# mcu_v05.net
KiCad netlist of a schematic drawn in EAGLE
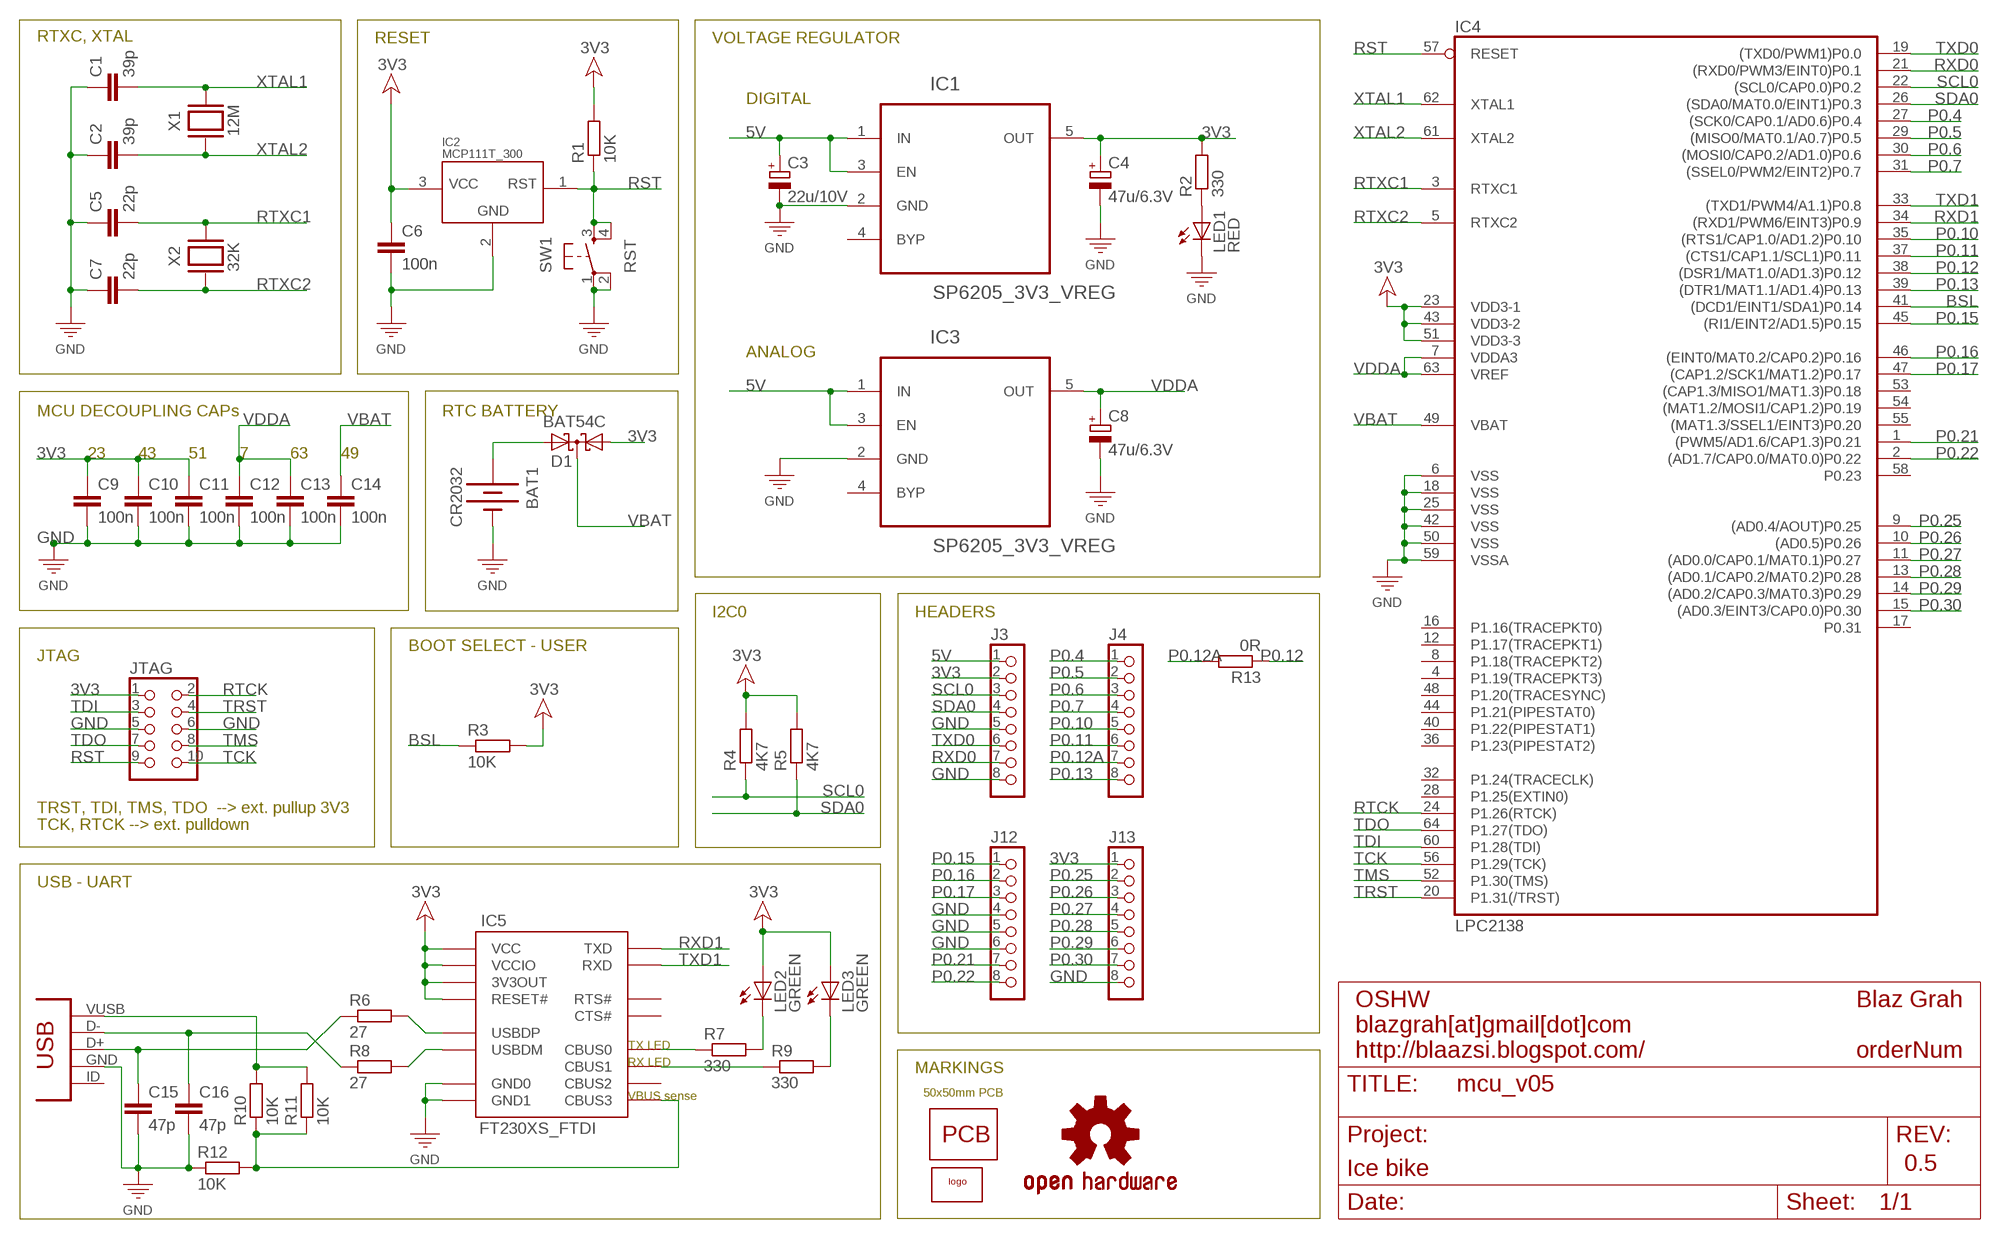
[diagram p0: schematic, sheet 1]

(export (version "E")
  (design (tool "Eeschema 10.0.6"))
  (components
    (comp (ref "BAT1")
      (value "CR2032")
      (footprint "eagle-import:BATTERY_20MM_SMD")
      (libsource (lib "eagle-import") (part "BATTERY20MM"))
    )
    (comp (ref "C1")
      (value "39p")
      (footprint "eagle-import:C0603")
      (libsource (lib "eagle-import") (part "C-EUC0603"))
    )
    (comp (ref "C2")
      (value "39p")
      (footprint "eagle-import:C0603")
      (libsource (lib "eagle-import") (part "C-EUC0603"))
    )
    (comp (ref "C3")
      (value "22u/10V")
      (footprint "eagle-import:SMC_B")
      (libsource (lib "eagle-import") (part "CAPACITOR_POL-SMC_B"))
    )
    (comp (ref "C4")
      (value "47u/6.3V")
      (footprint "eagle-import:SMC_B")
      (libsource (lib "eagle-import") (part "CAPACITOR_POL-SMC_B"))
    )
    (comp (ref "C5")
      (value "22p")
      (footprint "eagle-import:C0603")
      (libsource (lib "eagle-import") (part "C-EUC0603"))
    )
    (comp (ref "C6")
      (value "100n")
      (footprint "eagle-import:C0603")
      (libsource (lib "eagle-import") (part "C-EUC0603"))
    )
    (comp (ref "C7")
      (value "22p")
      (footprint "eagle-import:C0603")
      (libsource (lib "eagle-import") (part "C-EUC0603"))
    )
    (comp (ref "C8")
      (value "47u/6.3V")
      (footprint "eagle-import:SMC_B")
      (libsource (lib "eagle-import") (part "CAPACITOR_POL-SMC_B"))
    )
    (comp (ref "C9")
      (value "100n")
      (footprint "eagle-import:C0603")
      (libsource (lib "eagle-import") (part "C-EUC0603"))
    )
    (comp (ref "C10")
      (value "100n")
      (footprint "eagle-import:C0603")
      (libsource (lib "eagle-import") (part "C-EUC0603"))
    )
    (comp (ref "C11")
      (value "100n")
      (footprint "eagle-import:C0603")
      (libsource (lib "eagle-import") (part "C-EUC0603"))
    )
    (comp (ref "C12")
      (value "100n")
      (footprint "eagle-import:C0603")
      (libsource (lib "eagle-import") (part "C-EUC0603"))
    )
    (comp (ref "C13")
      (value "100n")
      (footprint "eagle-import:C0603")
      (libsource (lib "eagle-import") (part "C-EUC0603"))
    )
    (comp (ref "C14")
      (value "100n")
      (footprint "eagle-import:C0603")
      (libsource (lib "eagle-import") (part "C-EUC0603"))
    )
    (comp (ref "C15")
      (value "47p")
      (footprint "eagle-import:C0603")
      (libsource (lib "eagle-import") (part "C-EUC0603"))
    )
    (comp (ref "C16")
      (value "47p")
      (footprint "eagle-import:C0603")
      (libsource (lib "eagle-import") (part "C-EUC0603"))
    )
    (comp (ref "D1")
      (value "BAT54C")
      (footprint "eagle-import:SOT23")
      (libsource (lib "eagle-import") (part "BAT54C"))
    )
    (comp (ref "DOC")
      (value "FRAME_DINA4_L")
      (footprint "eagle-import:DP_LOGO")
      (fields
        (field (name "AUTHOR") "Blaz Grah")
        (field (name "DATE") "23.4.2012")
        (field (name "LICENSE") "OSHW")
        (field (name "PROJECT") "Ice bike")
        (field (name "REV") "0.5")
        (field (name "URL1") "blazgrah[at]gmail[dot]com")
        (field (name "URL2") "http://blaazsi.blogspot.com/")
      )
      (libsource (lib "eagle-import") (part "FRAME_DINA4_L"))
    )
    (comp (ref "IC1")
      (value "SP6205_3V3_VREG")
      (footprint "eagle-import:SOT23-5")
      (libsource (lib "eagle-import") (part "SP6205_3V3_VREG"))
    )
    (comp (ref "IC2")
      (value "MCP111T_300")
      (footprint "eagle-import:SOT23")
      (libsource (lib "eagle-import") (part "MCP111T_300"))
    )
    (comp (ref "IC3")
      (value "SP6205_3V3_VREG")
      (footprint "eagle-import:SOT23-5")
      (libsource (lib "eagle-import") (part "SP6205_3V3_VREG"))
    )
    (comp (ref "IC4")
      (value "LPC2138")
      (footprint "eagle-import:LQFP64")
      (libsource (lib "eagle-import") (part "LCP2138_LQFP64"))
    )
    (comp (ref "IC5")
      (value "FT230XS_FTDI")
      (footprint "eagle-import:SSOP16")
      (libsource (lib "eagle-import") (part "FT230XS_FTDI"))
    )
    (comp (ref "J3")
      (value "CON_HEADER_1X08-PTH")
      (footprint "eagle-import:M1X8")
      (libsource (lib "eagle-import") (part "CON_HEADER_1X08-PTH"))
    )
    (comp (ref "J4")
      (value "CON_HEADER_1X08-PTH")
      (footprint "eagle-import:M1X8")
      (libsource (lib "eagle-import") (part "CON_HEADER_1X08-PTH"))
    )
    (comp (ref "J12")
      (value "CON_HEADER_1X08-PTH")
      (footprint "eagle-import:M1X8")
      (libsource (lib "eagle-import") (part "CON_HEADER_1X08-PTH"))
    )
    (comp (ref "J13")
      (value "CON_HEADER_1X08-PTH")
      (footprint "eagle-import:M1X8")
      (libsource (lib "eagle-import") (part "CON_HEADER_1X08-PTH"))
    )
    (comp (ref "JTAG")
      (value "CON_HEADER_2X05-PTH+SHROUDED_A")
      (footprint "eagle-import:PINSHRD_PTH_2X05")
      (libsource (lib "eagle-import") (part "CON_HEADER_2X05-PTH+SHROUDED_A"))
    )
    (comp (ref "LED1")
      (value "RED")
      (footprint "eagle-import:LED0805")
      (libsource (lib "eagle-import") (part "LED0805"))
    )
    (comp (ref "LED2")
      (value "GREEN")
      (footprint "eagle-import:LED0805")
      (libsource (lib "eagle-import") (part "LED0805"))
    )
    (comp (ref "LED3")
      (value "GREEN")
      (footprint "eagle-import:LED0805")
      (libsource (lib "eagle-import") (part "LED0805"))
    )
    (comp (ref "LOGO1")
      (value "OSHW-LOGOS")
      (footprint "eagle-import:OSHW-LOGO-S")
      (libsource (lib "eagle-import") (part "OSHW-LOGOS"))
    )
    (comp (ref "PCB1")
      (value "PCB")
      (footprint "eagle-import:PCB_50X50")
      (libsource (lib "eagle-import") (part "PCB"))
    )
    (comp (ref "R1")
      (value "10K")
      (footprint "eagle-import:R0603")
      (libsource (lib "eagle-import") (part "R-EU0603"))
    )
    (comp (ref "R2")
      (value "330")
      (footprint "eagle-import:R0603")
      (libsource (lib "eagle-import") (part "R-EU0603"))
    )
    (comp (ref "R3")
      (value "10K")
      (footprint "eagle-import:R0603")
      (libsource (lib "eagle-import") (part "R-EU0603"))
    )
    (comp (ref "R4")
      (value "4K7")
      (footprint "eagle-import:R0603")
      (libsource (lib "eagle-import") (part "R-EU0603"))
    )
    (comp (ref "R5")
      (value "4K7")
      (footprint "eagle-import:R0603")
      (libsource (lib "eagle-import") (part "R-EU0603"))
    )
    (comp (ref "R6")
      (value "27")
      (footprint "eagle-import:R0603")
      (libsource (lib "eagle-import") (part "R-EU0603"))
    )
    (comp (ref "R7")
      (value "330")
      (footprint "eagle-import:R0603")
      (libsource (lib "eagle-import") (part "R-EU0603"))
    )
    (comp (ref "R8")
      (value "27")
      (footprint "eagle-import:R0603")
      (libsource (lib "eagle-import") (part "R-EU0603"))
    )
    (comp (ref "R9")
      (value "330")
      (footprint "eagle-import:R0603")
      (libsource (lib "eagle-import") (part "R-EU0603"))
    )
    (comp (ref "R10")
      (value "10K")
      (footprint "eagle-import:R0603")
      (libsource (lib "eagle-import") (part "R-EU0603"))
    )
    (comp (ref "R11")
      (value "10K")
      (footprint "eagle-import:R0603")
      (libsource (lib "eagle-import") (part "R-EU0603"))
    )
    (comp (ref "R12")
      (value "10K")
      (footprint "eagle-import:R0603")
      (libsource (lib "eagle-import") (part "R-EU0603"))
    )
    (comp (ref "R13")
      (value "0R")
      (footprint "eagle-import:R0603_JUMP")
      (libsource (lib "eagle-import") (part "R-EU0603J"))
    )
    (comp (ref "SW1")
      (value "RST")
      (footprint "eagle-import:BUTTON_SW_4P_SMD")
      (libsource (lib "eagle-import") (part "TACTIL_BUTTON"))
    )
    (comp (ref "U$13")
      (value "LOGO")
      (footprint "eagle-import:LOGO_SMILE")
      (libsource (lib "eagle-import") (part "LOGO"))
    )
    (comp (ref "USB1")
      (value "CON-USB-F-MINI-B")
      (footprint "eagle-import:CONN_USB_MINI-B")
      (libsource (lib "eagle-import") (part "CON-USB-F-MINI-B"))
    )
    (comp (ref "X1")
      (value "12M")
      (footprint "eagle-import:CRYSTAL_12M_4.8X10.6MM")
      (libsource (lib "eagle-import") (part "CRYSTALSMD_4.8X10.6"))
    )
    (comp (ref "X2")
      (value "32K")
      (footprint "eagle-import:CRYSTAL_32K_SMD")
      (libsource (lib "eagle-import") (part "CRYSTALSMD_32K"))
    )
  )
  (nets
    (net (code "1") (name "/5V") (class "Default")
      (node (ref "C3") (pin "+") (pinfunction "+_+") (pintype "passive"))
      (node (ref "IC1") (pin "1") (pinfunction "IN_1") (pintype "input"))
      (node (ref "IC1") (pin "3") (pinfunction "EN_3") (pintype "input"))
      (node (ref "IC3") (pin "1") (pinfunction "IN_1") (pintype "input"))
      (node (ref "IC3") (pin "3") (pinfunction "EN_3") (pintype "input"))
      (node (ref "J3") (pin "1") (pinfunction "1_1") (pintype "passive"))
    )
    (net (code "2") (name "/BSL") (class "Default")
      (node (ref "IC4") (pin "41") (pinfunction "(DCD1/EINT1/SDA1)P0.14_41") (pintype "bidirectional"))
      (node (ref "R3") (pin "1") (pinfunction "1_1") (pintype "passive"))
    )
    (net (code "3") (name "/P0.4") (class "Default")
      (node (ref "IC4") (pin "27") (pinfunction "(SCK0/CAP0.1/AD0.6)P0.4_27") (pintype "bidirectional"))
      (node (ref "J4") (pin "1") (pinfunction "1_1") (pintype "passive"))
    )
    (net (code "4") (name "/P0.5") (class "Default")
      (node (ref "IC4") (pin "29") (pinfunction "(MISO0/MAT0.1/A0.7)P0.5_29") (pintype "bidirectional"))
      (node (ref "J4") (pin "2") (pinfunction "2_2") (pintype "passive"))
    )
    (net (code "5") (name "/P0.6") (class "Default")
      (node (ref "IC4") (pin "30") (pinfunction "(MOSI0/CAP0.2/AD1.0)P0.6_30") (pintype "bidirectional"))
      (node (ref "J4") (pin "3") (pinfunction "3_3") (pintype "passive"))
    )
    (net (code "6") (name "/P0.7") (class "Default")
      (node (ref "IC4") (pin "31") (pinfunction "(SSEL0/PWM2/EINT2)P0.7_31") (pintype "bidirectional"))
      (node (ref "J4") (pin "4") (pinfunction "4_4") (pintype "passive"))
    )
    (net (code "7") (name "/P0.10") (class "Default")
      (node (ref "IC4") (pin "35") (pinfunction "(RTS1/CAP1.0/AD1.2)P0.10_35") (pintype "bidirectional"))
      (node (ref "J4") (pin "5") (pinfunction "5_5") (pintype "passive"))
    )
    (net (code "8") (name "/P0.11") (class "Default")
      (node (ref "IC4") (pin "37") (pinfunction "(CTS1/CAP1.1/SCL1)P0.11_37") (pintype "bidirectional"))
      (node (ref "J4") (pin "6") (pinfunction "6_6") (pintype "passive"))
    )
    (net (code "9") (name "/P0.12") (class "Default")
      (node (ref "IC4") (pin "38") (pinfunction "(DSR1/MAT1.0/AD1.3)P0.12_38") (pintype "bidirectional"))
      (node (ref "R13") (pin "1") (pinfunction "1_1") (pintype "passive"))
    )
    (net (code "10") (name "/P0.12A") (class "Default")
      (node (ref "J4") (pin "7") (pinfunction "7_7") (pintype "passive"))
      (node (ref "R13") (pin "2") (pinfunction "2_2") (pintype "passive"))
    )
    (net (code "11") (name "/P0.13") (class "Default")
      (node (ref "IC4") (pin "39") (pinfunction "(DTR1/MAT1.1/AD1.4)P0.13_39") (pintype "bidirectional"))
      (node (ref "J4") (pin "8") (pinfunction "8_8") (pintype "passive"))
    )
    (net (code "12") (name "/P0.15") (class "Default")
      (node (ref "IC4") (pin "45") (pinfunction "(RI1/EINT2/AD1.5)P0.15_45") (pintype "bidirectional"))
      (node (ref "J12") (pin "1") (pinfunction "1_1") (pintype "passive"))
    )
    (net (code "13") (name "/P0.16") (class "Default")
      (node (ref "IC4") (pin "46") (pinfunction "(EINT0/MAT0.2/CAP0.2)P0.16_46") (pintype "bidirectional"))
      (node (ref "J12") (pin "2") (pinfunction "2_2") (pintype "passive"))
    )
    (net (code "14") (name "/P0.17") (class "Default")
      (node (ref "IC4") (pin "47") (pinfunction "(CAP1.2/SCK1/MAT1.2)P0.17_47") (pintype "bidirectional"))
      (node (ref "J12") (pin "3") (pinfunction "3_3") (pintype "passive"))
    )
    (net (code "15") (name "/P0.21") (class "Default")
      (node (ref "IC4") (pin "1") (pinfunction "(PWM5/AD1.6/CAP1.3)P0.21_1") (pintype "bidirectional"))
      (node (ref "J12") (pin "7") (pinfunction "7_7") (pintype "passive"))
    )
    (net (code "16") (name "/P0.22") (class "Default")
      (node (ref "IC4") (pin "2") (pinfunction "(AD1.7/CAP0.0/MAT0.0)P0.22_2") (pintype "bidirectional"))
      (node (ref "J12") (pin "8") (pinfunction "8_8") (pintype "passive"))
    )
    (net (code "17") (name "/P0.25") (class "Default")
      (node (ref "IC4") (pin "9") (pinfunction "(AD0.4/AOUT)P0.25_9") (pintype "bidirectional"))
      (node (ref "J13") (pin "2") (pinfunction "2_2") (pintype "passive"))
    )
    (net (code "18") (name "/P0.26") (class "Default")
      (node (ref "IC4") (pin "10") (pinfunction "(AD0.5)P0.26_10") (pintype "bidirectional"))
      (node (ref "J13") (pin "3") (pinfunction "3_3") (pintype "passive"))
    )
    (net (code "19") (name "/P0.27") (class "Default")
      (node (ref "IC4") (pin "11") (pinfunction "(AD0.0/CAP0.1/MAT0.1)P0.27_11") (pintype "bidirectional"))
      (node (ref "J13") (pin "4") (pinfunction "4_4") (pintype "passive"))
    )
    (net (code "20") (name "/P0.28") (class "Default")
      (node (ref "IC4") (pin "13") (pinfunction "(AD0.1/CAP0.2/MAT0.2)P0.28_13") (pintype "bidirectional"))
      (node (ref "J13") (pin "5") (pinfunction "5_5") (pintype "passive"))
    )
    (net (code "21") (name "/P0.29") (class "Default")
      (node (ref "IC4") (pin "14") (pinfunction "(AD0.2/CAP0.3/MAT0.3)P0.29_14") (pintype "bidirectional"))
      (node (ref "J13") (pin "6") (pinfunction "6_6") (pintype "passive"))
    )
    (net (code "22") (name "/P0.30") (class "Default")
      (node (ref "IC4") (pin "15") (pinfunction "(AD0.3/EINT3/CAP0.0)P0.30_15") (pintype "bidirectional"))
      (node (ref "J13") (pin "7") (pinfunction "7_7") (pintype "passive"))
    )
    (net (code "23") (name "/RST") (class "Default")
      (node (ref "IC2") (pin "1") (pinfunction "RST_1") (pintype "output"))
      (node (ref "IC4") (pin "57") (pinfunction "RESET_57") (pintype "input"))
      (node (ref "JTAG") (pin "9") (pinfunction "9_9") (pintype "passive"))
      (node (ref "R1") (pin "1") (pinfunction "1_1") (pintype "passive"))
      (node (ref "SW1") (pin "3") (pinfunction "3_3") (pintype "passive"))
      (node (ref "SW1") (pin "4") (pinfunction "4_4") (pintype "passive"))
    )
    (net (code "24") (name "/RTCK") (class "Default")
      (node (ref "IC4") (pin "24") (pinfunction "P1.26(RTCK)_24") (pintype "bidirectional"))
      (node (ref "JTAG") (pin "2") (pinfunction "2_2") (pintype "passive"))
    )
    (net (code "25") (name "/RTXC1") (class "Default")
      (node (ref "C5") (pin "2") (pinfunction "2_2") (pintype "passive"))
      (node (ref "IC4") (pin "3") (pinfunction "RTXC1_3") (pintype "input"))
      (node (ref "X2") (pin "X2") (pinfunction "2_X2") (pintype "passive"))
    )
    (net (code "26") (name "/RTXC2") (class "Default")
      (node (ref "C7") (pin "2") (pinfunction "2_2") (pintype "passive"))
      (node (ref "IC4") (pin "5") (pinfunction "RTXC2_5") (pintype "output"))
      (node (ref "X2") (pin "X1") (pinfunction "1_X1") (pintype "passive"))
    )
    (net (code "27") (name "/RXD0") (class "Default")
      (node (ref "IC4") (pin "21") (pinfunction "(RXD0/PWM3/EINT0)P0.1_21") (pintype "bidirectional"))
      (node (ref "J3") (pin "7") (pinfunction "7_7") (pintype "passive"))
    )
    (net (code "28") (name "/RXD1") (class "Default")
      (node (ref "IC4") (pin "34") (pinfunction "(RXD1/PWM6/EINT3)P0.9_34") (pintype "bidirectional"))
      (node (ref "IC5") (pin "P$1") (pinfunction "TXD_P$1") (pintype "bidirectional"))
    )
    (net (code "29") (name "/SCL0") (class "Default")
      (node (ref "IC4") (pin "22") (pinfunction "(SCL0/CAP0.0)P0.2_22") (pintype "bidirectional"))
      (node (ref "J3") (pin "3") (pinfunction "3_3") (pintype "passive"))
      (node (ref "R4") (pin "1") (pinfunction "1_1") (pintype "passive"))
    )
    (net (code "30") (name "/SDA0") (class "Default")
      (node (ref "IC4") (pin "26") (pinfunction "(SDA0/MAT0.0/EINT1)P0.3_26") (pintype "bidirectional"))
      (node (ref "J3") (pin "4") (pinfunction "4_4") (pintype "passive"))
      (node (ref "R5") (pin "1") (pinfunction "1_1") (pintype "passive"))
    )
    (net (code "31") (name "/TCK") (class "Default")
      (node (ref "IC4") (pin "56") (pinfunction "P1.29(TCK)_56") (pintype "bidirectional"))
      (node (ref "JTAG") (pin "10") (pinfunction "10_10") (pintype "passive"))
    )
    (net (code "32") (name "/TDI") (class "Default")
      (node (ref "IC4") (pin "60") (pinfunction "P1.28(TDI)_60") (pintype "bidirectional"))
      (node (ref "JTAG") (pin "3") (pinfunction "3_3") (pintype "passive"))
    )
    (net (code "33") (name "/TDO") (class "Default")
      (node (ref "IC4") (pin "64") (pinfunction "P1.27(TDO)_64") (pintype "bidirectional"))
      (node (ref "JTAG") (pin "7") (pinfunction "7_7") (pintype "passive"))
    )
    (net (code "34") (name "/TMS") (class "Default")
      (node (ref "IC4") (pin "52") (pinfunction "P1.30(TMS)_52") (pintype "bidirectional"))
      (node (ref "JTAG") (pin "8") (pinfunction "8_8") (pintype "passive"))
    )
    (net (code "35") (name "/TRST") (class "Default")
      (node (ref "IC4") (pin "20") (pinfunction "P1.31(/TRST)_20") (pintype "bidirectional"))
      (node (ref "JTAG") (pin "4") (pinfunction "4_4") (pintype "passive"))
    )
    (net (code "36") (name "/TXD0") (class "Default")
      (node (ref "IC4") (pin "19") (pinfunction "(TXD0/PWM1)P0.0_19") (pintype "bidirectional"))
      (node (ref "J3") (pin "6") (pinfunction "6_6") (pintype "passive"))
    )
    (net (code "37") (name "/TXD1") (class "Default")
      (node (ref "IC4") (pin "33") (pinfunction "(TXD1/PWM4/A1.1)P0.8_33") (pintype "bidirectional"))
      (node (ref "IC5") (pin "P$4") (pinfunction "RXD_P$4") (pintype "bidirectional"))
    )
    (net (code "38") (name "/VBAT") (class "Default")
      (node (ref "C14") (pin "1") (pinfunction "1_1") (pintype "passive"))
      (node (ref "D1") (pin "3") (pinfunction "CC_3") (pintype "passive"))
      (node (ref "IC4") (pin "49") (pinfunction "VBAT_49") (pintype "power_in"))
    )
    (net (code "39") (name "/VDDA") (class "Default")
      (node (ref "C12") (pin "1") (pinfunction "1_1") (pintype "passive"))
      (node (ref "C13") (pin "1") (pinfunction "1_1") (pintype "passive"))
      (node (ref "C8") (pin "+") (pinfunction "+_+") (pintype "passive"))
      (node (ref "IC3") (pin "5") (pinfunction "OUT_5") (pintype "power_in"))
      (node (ref "IC4") (pin "63") (pinfunction "VREF_63") (pintype "input"))
      (node (ref "IC4") (pin "7") (pinfunction "VDDA3_7") (pintype "power_in"))
    )
    (net (code "40") (name "/XTAL1") (class "Default")
      (node (ref "C1") (pin "2") (pinfunction "2_2") (pintype "passive"))
      (node (ref "IC4") (pin "62") (pinfunction "XTAL1_62") (pintype "input"))
      (node (ref "X1") (pin "P$2") (pinfunction "2_P$2") (pintype "passive"))
    )
    (net (code "41") (name "/XTAL2") (class "Default")
      (node (ref "C2") (pin "2") (pinfunction "2_2") (pintype "passive"))
      (node (ref "IC4") (pin "61") (pinfunction "XTAL2_61") (pintype "output"))
      (node (ref "X1") (pin "P$1") (pinfunction "1_P$1") (pintype "passive"))
    )
    (net (code "42") (name "3V3") (class "Default")
      (node (ref "C10") (pin "1") (pinfunction "1_1") (pintype "passive"))
      (node (ref "C11") (pin "1") (pinfunction "1_1") (pintype "passive"))
      (node (ref "C4") (pin "+") (pinfunction "+_+") (pintype "passive"))
      (node (ref "C6") (pin "1") (pinfunction "1_1") (pintype "passive"))
      (node (ref "C9") (pin "1") (pinfunction "1_1") (pintype "passive"))
      (node (ref "D1") (pin "1") (pinfunction "A1_1") (pintype "passive"))
      (node (ref "IC1") (pin "5") (pinfunction "OUT_5") (pintype "power_in"))
      (node (ref "IC2") (pin "3") (pinfunction "VCC_3") (pintype "input"))
      (node (ref "IC4") (pin "23") (pinfunction "VDD3-1_23") (pintype "power_in"))
      (node (ref "IC4") (pin "43") (pinfunction "VDD3-2_43") (pintype "power_in"))
      (node (ref "IC4") (pin "51") (pinfunction "VDD3-3_51") (pintype "power_in"))
      (node (ref "IC5") (pin "P$10") (pinfunction "3V3OUT_P$10") (pintype "power_in"))
      (node (ref "IC5") (pin "P$11") (pinfunction "RESET#_P$11") (pintype "bidirectional"))
      (node (ref "IC5") (pin "P$12") (pinfunction "VCC_P$12") (pintype "power_in"))
      (node (ref "IC5") (pin "P$3") (pinfunction "VCCIO_P$3") (pintype "power_in"))
      (node (ref "J13") (pin "1") (pinfunction "1_1") (pintype "passive"))
      (node (ref "J3") (pin "2") (pinfunction "2_2") (pintype "passive"))
      (node (ref "JTAG") (pin "1") (pinfunction "1_1") (pintype "passive"))
      (node (ref "LED2") (pin "A") (pinfunction "A_A") (pintype "passive"))
      (node (ref "LED3") (pin "A") (pinfunction "A_A") (pintype "passive"))
      (node (ref "R1") (pin "2") (pinfunction "2_2") (pintype "passive"))
      (node (ref "R2") (pin "2") (pinfunction "2_2") (pintype "passive"))
      (node (ref "R3") (pin "2") (pinfunction "2_2") (pintype "passive"))
      (node (ref "R4") (pin "2") (pinfunction "2_2") (pintype "passive"))
      (node (ref "R5") (pin "2") (pinfunction "2_2") (pintype "passive"))
    )
    (net (code "43") (name "GND") (class "Default")
      (node (ref "BAT1") (pin "NEG") (pinfunction "NEG_NEG") (pintype "power_in"))
      (node (ref "C1") (pin "1") (pinfunction "1_1") (pintype "passive"))
      (node (ref "C10") (pin "2") (pinfunction "2_2") (pintype "passive"))
      (node (ref "C11") (pin "2") (pinfunction "2_2") (pintype "passive"))
      (node (ref "C12") (pin "2") (pinfunction "2_2") (pintype "passive"))
      (node (ref "C13") (pin "2") (pinfunction "2_2") (pintype "passive"))
      (node (ref "C14") (pin "2") (pinfunction "2_2") (pintype "passive"))
      (node (ref "C15") (pin "2") (pinfunction "2_2") (pintype "passive"))
      (node (ref "C16") (pin "2") (pinfunction "2_2") (pintype "passive"))
      (node (ref "C2") (pin "1") (pinfunction "1_1") (pintype "passive"))
      (node (ref "C3") (pin "-") (pinfunction "-_-") (pintype "passive"))
      (node (ref "C4") (pin "-") (pinfunction "-_-") (pintype "passive"))
      (node (ref "C5") (pin "1") (pinfunction "1_1") (pintype "passive"))
      (node (ref "C6") (pin "2") (pinfunction "2_2") (pintype "passive"))
      (node (ref "C7") (pin "1") (pinfunction "1_1") (pintype "passive"))
      (node (ref "C8") (pin "-") (pinfunction "-_-") (pintype "passive"))
      (node (ref "C9") (pin "2") (pinfunction "2_2") (pintype "passive"))
      (node (ref "IC1") (pin "2") (pinfunction "GND_2") (pintype "power_in"))
      (node (ref "IC2") (pin "2") (pinfunction "GND_2") (pintype "power_in"))
      (node (ref "IC3") (pin "2") (pinfunction "GND_2") (pintype "power_in"))
      (node (ref "IC4") (pin "18") (pinfunction "VSS_18") (pintype "power_in"))
      (node (ref "IC4") (pin "25") (pinfunction "VSS_25") (pintype "power_in"))
      (node (ref "IC4") (pin "42") (pinfunction "VSS_42") (pintype "power_in"))
      (node (ref "IC4") (pin "50") (pinfunction "VSS_50") (pintype "power_in"))
      (node (ref "IC4") (pin "59") (pinfunction "VSSA_59") (pintype "power_in"))
      (node (ref "IC4") (pin "6") (pinfunction "VSS_6") (pintype "power_in"))
      (node (ref "IC5") (pin "P$13") (pinfunction "GND1_P$13") (pintype "power_in"))
      (node (ref "IC5") (pin "P$5") (pinfunction "GND0_P$5") (pintype "power_in"))
      (node (ref "J12") (pin "4") (pinfunction "4_4") (pintype "passive"))
      (node (ref "J12") (pin "5") (pinfunction "5_5") (pintype "passive"))
      (node (ref "J12") (pin "6") (pinfunction "6_6") (pintype "passive"))
      (node (ref "J13") (pin "8") (pinfunction "8_8") (pintype "passive"))
      (node (ref "J3") (pin "5") (pinfunction "5_5") (pintype "passive"))
      (node (ref "J3") (pin "8") (pinfunction "8_8") (pintype "passive"))
      (node (ref "JTAG") (pin "5") (pinfunction "5_5") (pintype "passive"))
      (node (ref "JTAG") (pin "6") (pinfunction "6_6") (pintype "passive"))
      (node (ref "LED1") (pin "C") (pinfunction "C_C") (pintype "passive"))
      (node (ref "R12") (pin "1") (pinfunction "1_1") (pintype "passive"))
      (node (ref "SW1") (pin "1") (pinfunction "1_1") (pintype "passive"))
      (node (ref "SW1") (pin "2") (pinfunction "2_2") (pintype "passive"))
      (node (ref "USB1") (pin "GND") (pinfunction "GND_GND") (pintype "bidirectional"))
    )
    (net (code "44") (name "Net-(C15-Pad1)") (class "Default")
      (node (ref "C15") (pin "1") (pinfunction "1_1") (pintype "passive"))
      (node (ref "R6") (pin "1") (pinfunction "1_1") (pintype "passive"))
      (node (ref "USB1") (pin "D+") (pinfunction "D+_D+") (pintype "bidirectional"))
    )
    (net (code "45") (name "Net-(C16-Pad1)") (class "Default")
      (node (ref "C16") (pin "1") (pinfunction "1_1") (pintype "passive"))
      (node (ref "R8") (pin "1") (pinfunction "1_1") (pintype "passive"))
      (node (ref "USB1") (pin "D-") (pinfunction "D-_D-") (pintype "bidirectional"))
    )
    (net (code "46") (name "Net-(D1-A2)") (class "Default")
      (node (ref "BAT1") (pin "POS1") (pinfunction "POZ_POS1") (pintype "power_in"))
      (node (ref "BAT1") (pin "POS2") (pinfunction "POZ_POS2") (pintype "power_in"))
      (node (ref "D1") (pin "2") (pinfunction "A2_2") (pintype "passive"))
    )
    (net (code "47") (name "Net-(IC5-CBUS0)") (class "Default")
      (node (ref "IC5") (pin "P$15") (pinfunction "CBUS0_P$15") (pintype "bidirectional"))
      (node (ref "R7") (pin "1") (pinfunction "1_1") (pintype "passive"))
    )
    (net (code "48") (name "Net-(IC5-CBUS1)") (class "Default")
      (node (ref "IC5") (pin "P$14") (pinfunction "CBUS1_P$14") (pintype "bidirectional"))
      (node (ref "R9") (pin "1") (pinfunction "1_1") (pintype "passive"))
    )
    (net (code "49") (name "Net-(IC5-CBUS3)") (class "Default")
      (node (ref "IC5") (pin "P$16") (pinfunction "CBUS3_P$16") (pintype "bidirectional"))
      (node (ref "R10") (pin "1") (pinfunction "1_1") (pintype "passive"))
      (node (ref "R11") (pin "1") (pinfunction "1_1") (pintype "passive"))
      (node (ref "R12") (pin "2") (pinfunction "2_2") (pintype "passive"))
    )
    (net (code "50") (name "Net-(IC5-USBDM)") (class "Default")
      (node (ref "IC5") (pin "P$9") (pinfunction "USBDM_P$9") (pintype "bidirectional"))
      (node (ref "R8") (pin "2") (pinfunction "2_2") (pintype "passive"))
    )
    (net (code "51") (name "Net-(IC5-USBDP)") (class "Default")
      (node (ref "IC5") (pin "P$8") (pinfunction "USBDP_P$8") (pintype "bidirectional"))
      (node (ref "R6") (pin "2") (pinfunction "2_2") (pintype "passive"))
    )
    (net (code "52") (name "Net-(LED1-PadA)") (class "Default")
      (node (ref "LED1") (pin "A") (pinfunction "A_A") (pintype "passive"))
      (node (ref "R2") (pin "1") (pinfunction "1_1") (pintype "passive"))
    )
    (net (code "53") (name "Net-(LED2-PadC)") (class "Default")
      (node (ref "LED2") (pin "C") (pinfunction "C_C") (pintype "passive"))
      (node (ref "R7") (pin "2") (pinfunction "2_2") (pintype "passive"))
    )
    (net (code "54") (name "Net-(LED3-PadC)") (class "Default")
      (node (ref "LED3") (pin "C") (pinfunction "C_C") (pintype "passive"))
      (node (ref "R9") (pin "2") (pinfunction "2_2") (pintype "passive"))
    )
    (net (code "55") (name "Net-(R10-Pad2)") (class "Default")
      (node (ref "R10") (pin "2") (pinfunction "2_2") (pintype "passive"))
      (node (ref "R11") (pin "2") (pinfunction "2_2") (pintype "passive"))
      (node (ref "USB1") (pin "VUSB") (pinfunction "VUSB_VUSB") (pintype "bidirectional"))
    )
    (net (code "56") (name "unconnected-(IC1-BYP-Pad4)") (class "Default")
      (node (ref "IC1") (pin "4") (pinfunction "BYP_4") (pintype "no_connect"))
    )
    (net (code "57") (name "unconnected-(IC3-BYP-Pad4)") (class "Default")
      (node (ref "IC3") (pin "4") (pinfunction "BYP_4") (pintype "no_connect"))
    )
    (net (code "58") (name "unconnected-(IC4-(CAP1.3{slash}MISO1{slash}MAT1.3)P0.18-Pad53)") (class "Default")
      (node (ref "IC4") (pin "53") (pinfunction "(CAP1.3/MISO1/MAT1.3)P0.18_53") (pintype "bidirectional"))
    )
    (net (code "59") (name "unconnected-(IC4-(MAT1.2{slash}MOSI1{slash}CAP1.2)P0.19-Pad54)") (class "Default")
      (node (ref "IC4") (pin "54") (pinfunction "(MAT1.2/MOSI1/CAP1.2)P0.19_54") (pintype "bidirectional"))
    )
    (net (code "60") (name "unconnected-(IC4-(MAT1.3{slash}SSEL1{slash}EINT3)P0.20-Pad55)") (class "Default")
      (node (ref "IC4") (pin "55") (pinfunction "(MAT1.3/SSEL1/EINT3)P0.20_55") (pintype "bidirectional"))
    )
    (net (code "61") (name "unconnected-(IC4-P0.23-Pad58)") (class "Default")
      (node (ref "IC4") (pin "58") (pinfunction "P0.23_58") (pintype "bidirectional"))
    )
    (net (code "62") (name "unconnected-(IC4-P0.31-Pad17)") (class "Default")
      (node (ref "IC4") (pin "17") (pinfunction "P0.31_17") (pintype "output"))
    )
    (net (code "63") (name "unconnected-(IC4-P1.16(TRACEPKT0)-Pad16)") (class "Default")
      (node (ref "IC4") (pin "16") (pinfunction "P1.16(TRACEPKT0)_16") (pintype "bidirectional"))
    )
    (net (code "64") (name "unconnected-(IC4-P1.17(TRACEPKT1)-Pad12)") (class "Default")
      (node (ref "IC4") (pin "12") (pinfunction "P1.17(TRACEPKT1)_12") (pintype "bidirectional"))
    )
    (net (code "65") (name "unconnected-(IC4-P1.18(TRACEPKT2)-Pad8)") (class "Default")
      (node (ref "IC4") (pin "8") (pinfunction "P1.18(TRACEPKT2)_8") (pintype "bidirectional"))
    )
    (net (code "66") (name "unconnected-(IC4-P1.19(TRACEPKT3)-Pad4)") (class "Default")
      (node (ref "IC4") (pin "4") (pinfunction "P1.19(TRACEPKT3)_4") (pintype "bidirectional"))
    )
    (net (code "67") (name "unconnected-(IC4-P1.20(TRACESYNC)-Pad48)") (class "Default")
      (node (ref "IC4") (pin "48") (pinfunction "P1.20(TRACESYNC)_48") (pintype "bidirectional"))
    )
    (net (code "68") (name "unconnected-(IC4-P1.21(PIPESTAT0)-Pad44)") (class "Default")
      (node (ref "IC4") (pin "44") (pinfunction "P1.21(PIPESTAT0)_44") (pintype "bidirectional"))
    )
    (net (code "69") (name "unconnected-(IC4-P1.22(PIPESTAT1)-Pad40)") (class "Default")
      (node (ref "IC4") (pin "40") (pinfunction "P1.22(PIPESTAT1)_40") (pintype "bidirectional"))
    )
    (net (code "70") (name "unconnected-(IC4-P1.23(PIPESTAT2)-Pad36)") (class "Default")
      (node (ref "IC4") (pin "36") (pinfunction "P1.23(PIPESTAT2)_36") (pintype "bidirectional"))
    )
    (net (code "71") (name "unconnected-(IC4-P1.24(TRACECLK)-Pad32)") (class "Default")
      (node (ref "IC4") (pin "32") (pinfunction "P1.24(TRACECLK)_32") (pintype "bidirectional"))
    )
    (net (code "72") (name "unconnected-(IC4-P1.25(EXTIN0)-Pad28)") (class "Default")
      (node (ref "IC4") (pin "28") (pinfunction "P1.25(EXTIN0)_28") (pintype "bidirectional"))
    )
    (net (code "73") (name "unconnected-(IC5-CBUS2-PadP$7)") (class "Default")
      (node (ref "IC5") (pin "P$7") (pinfunction "CBUS2_P$7") (pintype "bidirectional"))
    )
    (net (code "74") (name "unconnected-(IC5-CTS#-PadP$6)") (class "Default")
      (node (ref "IC5") (pin "P$6") (pinfunction "CTS#_P$6") (pintype "bidirectional"))
    )
    (net (code "75") (name "unconnected-(IC5-RTS#-PadP$2)") (class "Default")
      (node (ref "IC5") (pin "P$2") (pinfunction "RTS#_P$2") (pintype "bidirectional"))
    )
    (net (code "76") (name "unconnected-(USB1B-USBID-PadID)") (class "Default")
      (node (ref "USB1") (pin "ID") (pinfunction "USBID_ID") (pintype "bidirectional"))
    )
  )
)
